# 601_GridPos6.net
KiCad netlist of a schematic drawn in Altium Designer
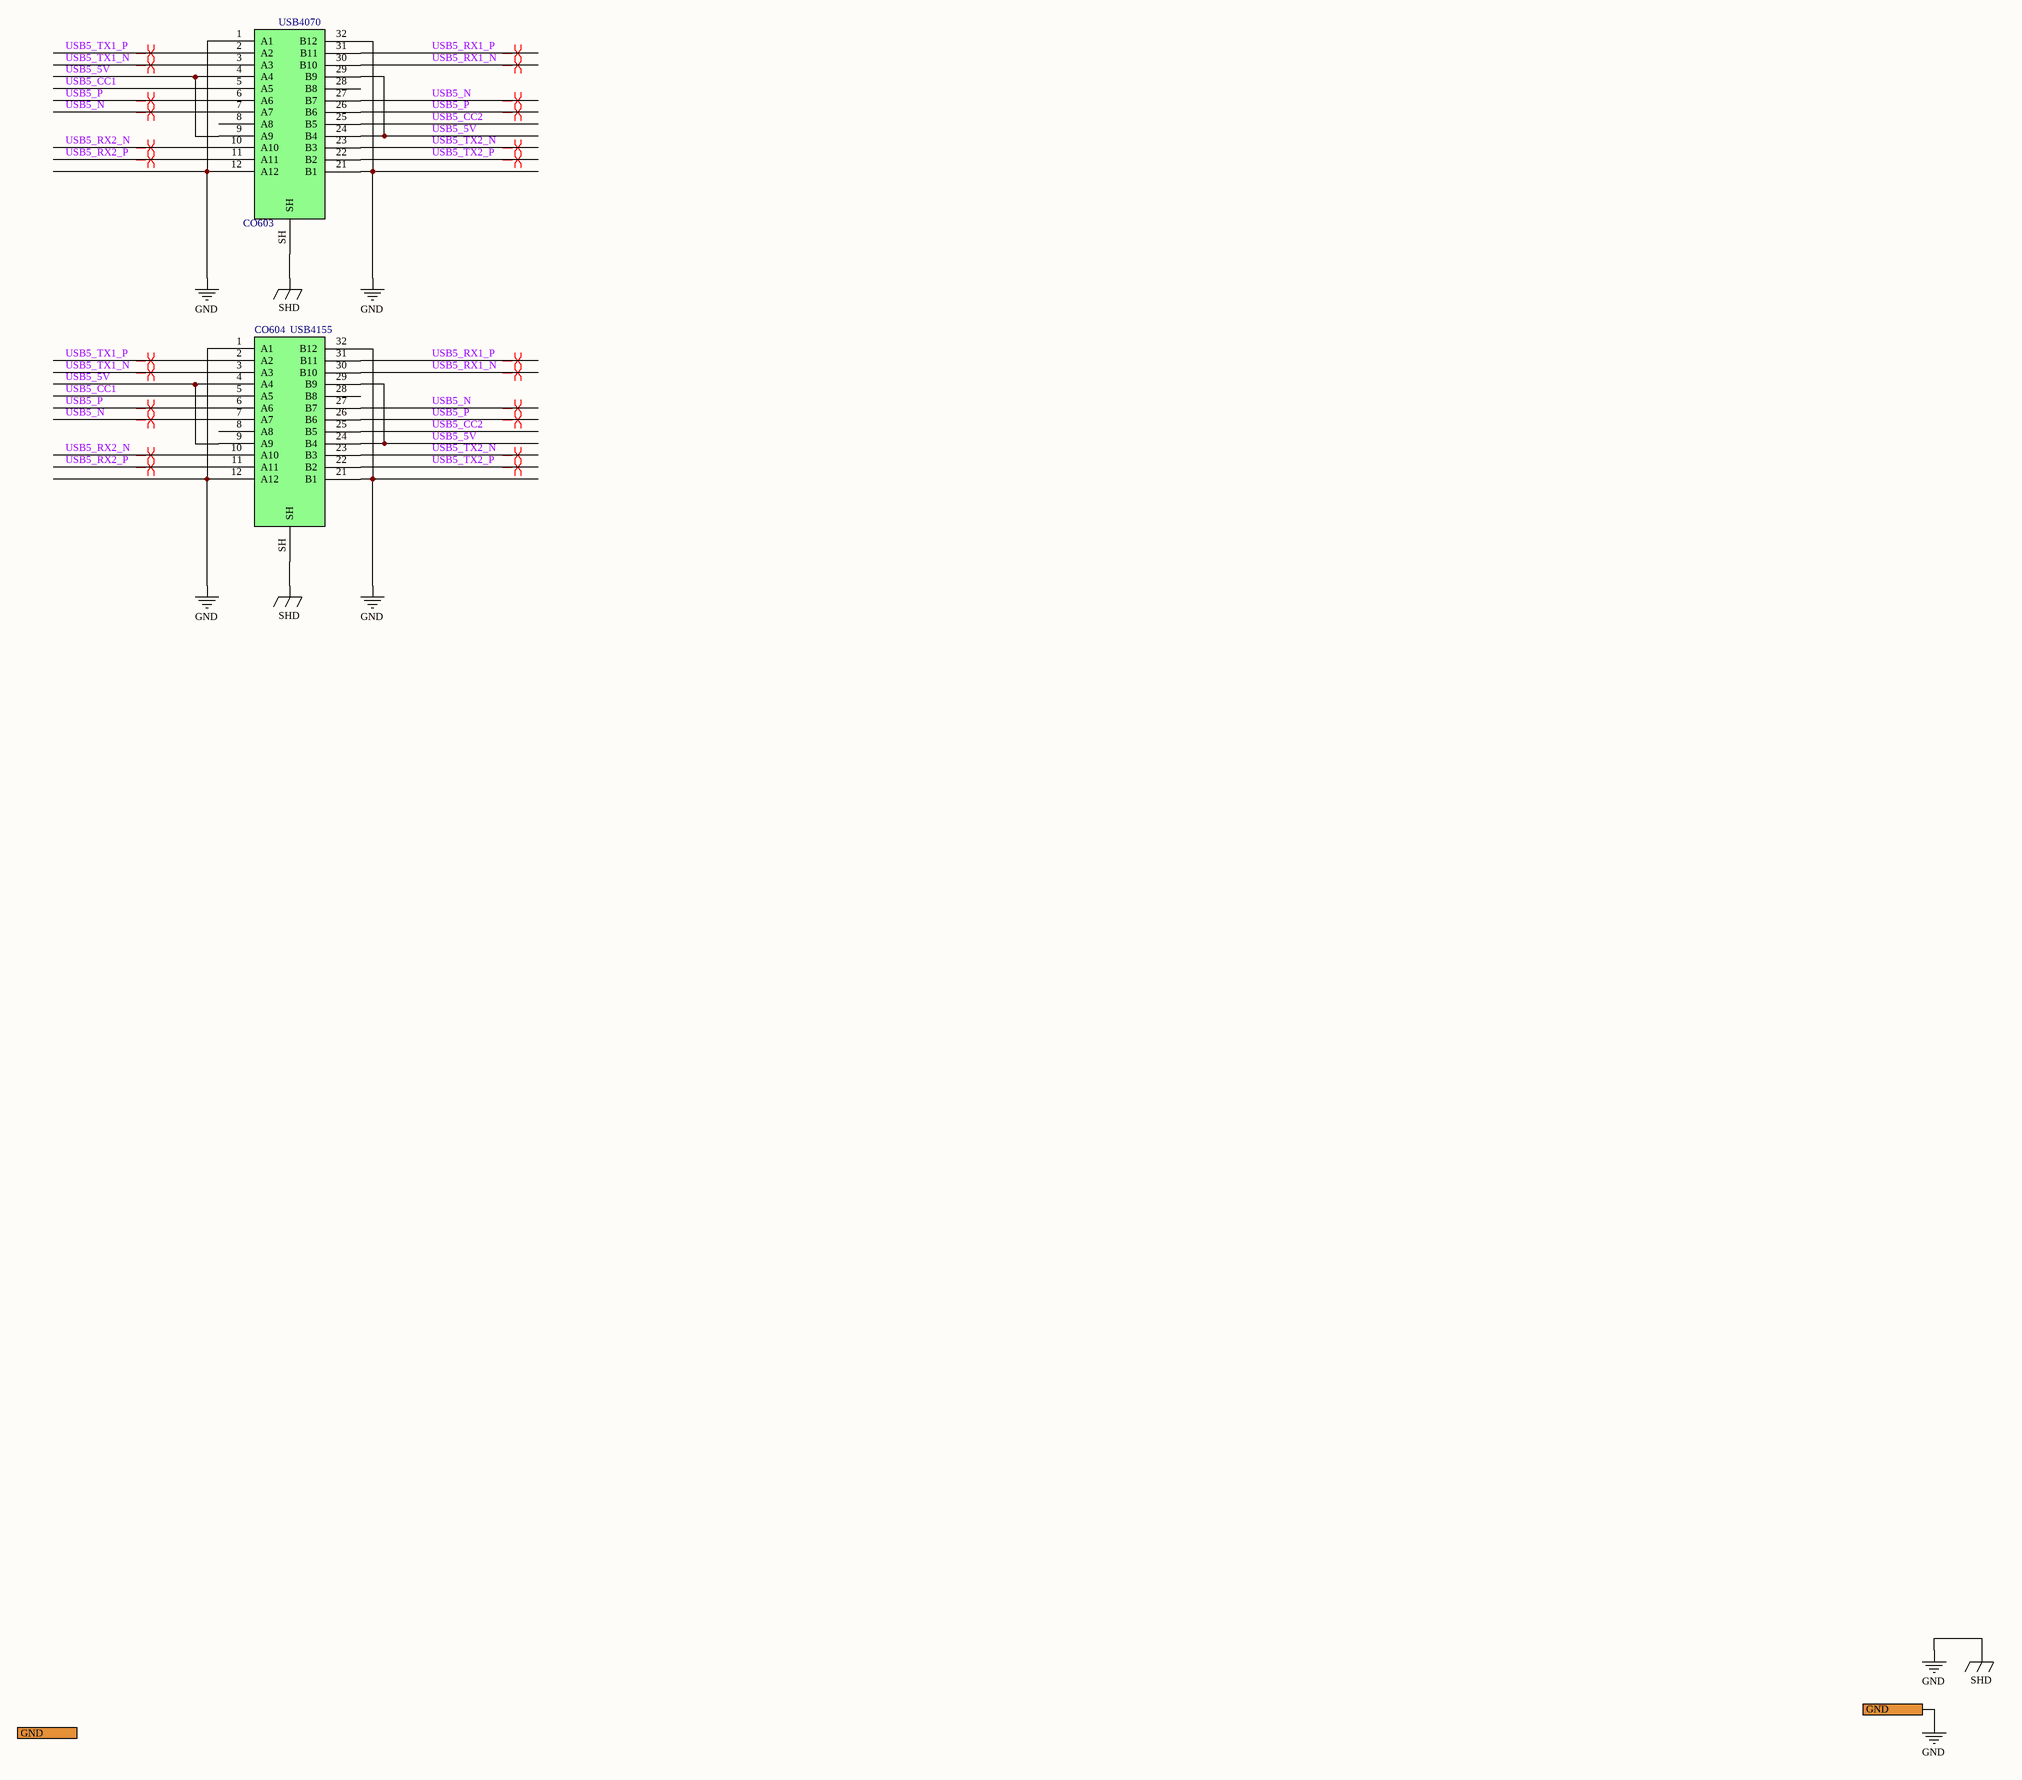
[diagram p0: 601_GridPos6.SchDoc]

(export (version "E")
  (design (tool "Eeschema 10.0.6"))
  (components
    (comp (ref "CO603")
      (value "USB4070")
      (footprint "USB4070-30-C")
      (description "USB C connector Receptacle Vertical")
      (fields
        (field (name "REFVAL") "USB4070")
        (field (name "PART NUMBER") "CO0021")
        (field (name "MANFACTPART") "USB4070-30-C")
      )
      (libsource (lib "GTS_Database") (part "USB-CC"))
    )
    (comp (ref "CO604")
      (value "USB4155")
      (footprint "USB4155-03-C")
      (description "USB C connector Plug Horizontal")
      (fields
        (field (name "REFVAL") "USB4155")
        (field (name "PART NUMBER") "CO0031")
        (field (name "MANFACTPART") "USB4155-03-C")
      )
      (libsource (lib "GTS_Database") (part "USB-CC"))
    )
  )
  (nets
    (net (code "1") (name "/USB5_5V") (class "Default")
      (node (ref "CO603") (pin "24") (pinfunction "B4_24") (pintype "passive"))
      (node (ref "CO603") (pin "29") (pinfunction "B9_29") (pintype "passive"))
      (node (ref "CO603") (pin "4") (pinfunction "A4_4") (pintype "passive"))
      (node (ref "CO603") (pin "9") (pinfunction "A9_9") (pintype "passive"))
      (node (ref "CO604") (pin "24") (pinfunction "B4_24") (pintype "passive"))
      (node (ref "CO604") (pin "29") (pinfunction "B9_29") (pintype "passive"))
      (node (ref "CO604") (pin "4") (pinfunction "A4_4") (pintype "passive"))
      (node (ref "CO604") (pin "9") (pinfunction "A9_9") (pintype "passive"))
    )
    (net (code "2") (name "/USB5_CC1") (class "Default")
      (node (ref "CO603") (pin "5") (pinfunction "A5_5") (pintype "passive"))
      (node (ref "CO604") (pin "5") (pinfunction "A5_5") (pintype "passive"))
    )
    (net (code "3") (name "/USB5_CC2") (class "Default")
      (node (ref "CO603") (pin "25") (pinfunction "B5_25") (pintype "passive"))
      (node (ref "CO604") (pin "25") (pinfunction "B5_25") (pintype "passive"))
    )
    (net (code "4") (name "/USB5_N") (class "Default")
      (node (ref "CO603") (pin "27") (pinfunction "B7_27") (pintype "passive"))
      (node (ref "CO603") (pin "7") (pinfunction "A7_7") (pintype "passive"))
      (node (ref "CO604") (pin "27") (pinfunction "B7_27") (pintype "passive"))
      (node (ref "CO604") (pin "7") (pinfunction "A7_7") (pintype "passive"))
    )
    (net (code "5") (name "/USB5_P") (class "Default")
      (node (ref "CO603") (pin "26") (pinfunction "B6_26") (pintype "passive"))
      (node (ref "CO603") (pin "6") (pinfunction "A6_6") (pintype "passive"))
      (node (ref "CO604") (pin "26") (pinfunction "B6_26") (pintype "passive"))
      (node (ref "CO604") (pin "6") (pinfunction "A6_6") (pintype "passive"))
    )
    (net (code "6") (name "/USB5_RX1_N") (class "Default")
      (node (ref "CO603") (pin "30") (pinfunction "B10_30") (pintype "passive"))
      (node (ref "CO604") (pin "30") (pinfunction "B10_30") (pintype "passive"))
    )
    (net (code "7") (name "/USB5_RX1_P") (class "Default")
      (node (ref "CO603") (pin "31") (pinfunction "B11_31") (pintype "passive"))
      (node (ref "CO604") (pin "31") (pinfunction "B11_31") (pintype "passive"))
    )
    (net (code "8") (name "/USB5_RX2_N") (class "Default")
      (node (ref "CO603") (pin "10") (pinfunction "A10_10") (pintype "passive"))
      (node (ref "CO604") (pin "10") (pinfunction "A10_10") (pintype "passive"))
    )
    (net (code "9") (name "/USB5_RX2_P") (class "Default")
      (node (ref "CO603") (pin "11") (pinfunction "A11_11") (pintype "passive"))
      (node (ref "CO604") (pin "11") (pinfunction "A11_11") (pintype "passive"))
    )
    (net (code "10") (name "/USB5_TX1_N") (class "Default")
      (node (ref "CO603") (pin "3") (pinfunction "A3_3") (pintype "passive"))
      (node (ref "CO604") (pin "3") (pinfunction "A3_3") (pintype "passive"))
    )
    (net (code "11") (name "/USB5_TX1_P") (class "Default")
      (node (ref "CO603") (pin "2") (pinfunction "A2_2") (pintype "passive"))
      (node (ref "CO604") (pin "2") (pinfunction "A2_2") (pintype "passive"))
    )
    (net (code "12") (name "/USB5_TX2_N") (class "Default")
      (node (ref "CO603") (pin "23") (pinfunction "B3_23") (pintype "passive"))
      (node (ref "CO604") (pin "23") (pinfunction "B3_23") (pintype "passive"))
    )
    (net (code "13") (name "/USB5_TX2_P") (class "Default")
      (node (ref "CO603") (pin "22") (pinfunction "B2_22") (pintype "passive"))
      (node (ref "CO604") (pin "22") (pinfunction "B2_22") (pintype "passive"))
    )
    (net (code "14") (name "GND") (class "Default")
      (node (ref "CO603") (pin "1") (pinfunction "A1_1") (pintype "passive"))
      (node (ref "CO603") (pin "12") (pinfunction "A12_12") (pintype "passive"))
      (node (ref "CO603") (pin "21") (pinfunction "B1_21") (pintype "passive"))
      (node (ref "CO603") (pin "32") (pinfunction "B12_32") (pintype "passive"))
      (node (ref "CO603") (pin "SH") (pinfunction "SH_SH") (pintype "power_in"))
      (node (ref "CO604") (pin "1") (pinfunction "A1_1") (pintype "passive"))
      (node (ref "CO604") (pin "12") (pinfunction "A12_12") (pintype "passive"))
      (node (ref "CO604") (pin "21") (pinfunction "B1_21") (pintype "passive"))
      (node (ref "CO604") (pin "32") (pinfunction "B12_32") (pintype "passive"))
      (node (ref "CO604") (pin "SH") (pinfunction "SH_SH") (pintype "power_in"))
    )
    (net (code "15") (name "unconnected-(CO603-A8-Pad8)") (class "Default")
      (node (ref "CO603") (pin "8") (pinfunction "A8_8") (pintype "passive"))
    )
    (net (code "16") (name "unconnected-(CO603-B8-Pad28)") (class "Default")
      (node (ref "CO603") (pin "28") (pinfunction "B8_28") (pintype "passive"))
    )
    (net (code "17") (name "unconnected-(CO604-A8-Pad8)") (class "Default")
      (node (ref "CO604") (pin "8") (pinfunction "A8_8") (pintype "passive"))
    )
    (net (code "18") (name "unconnected-(CO604-B8-Pad28)") (class "Default")
      (node (ref "CO604") (pin "28") (pinfunction "B8_28") (pintype "passive"))
    )
  )
)
